# DB10005_CAN.net
KiCad netlist of a schematic drawn in Altium Designer
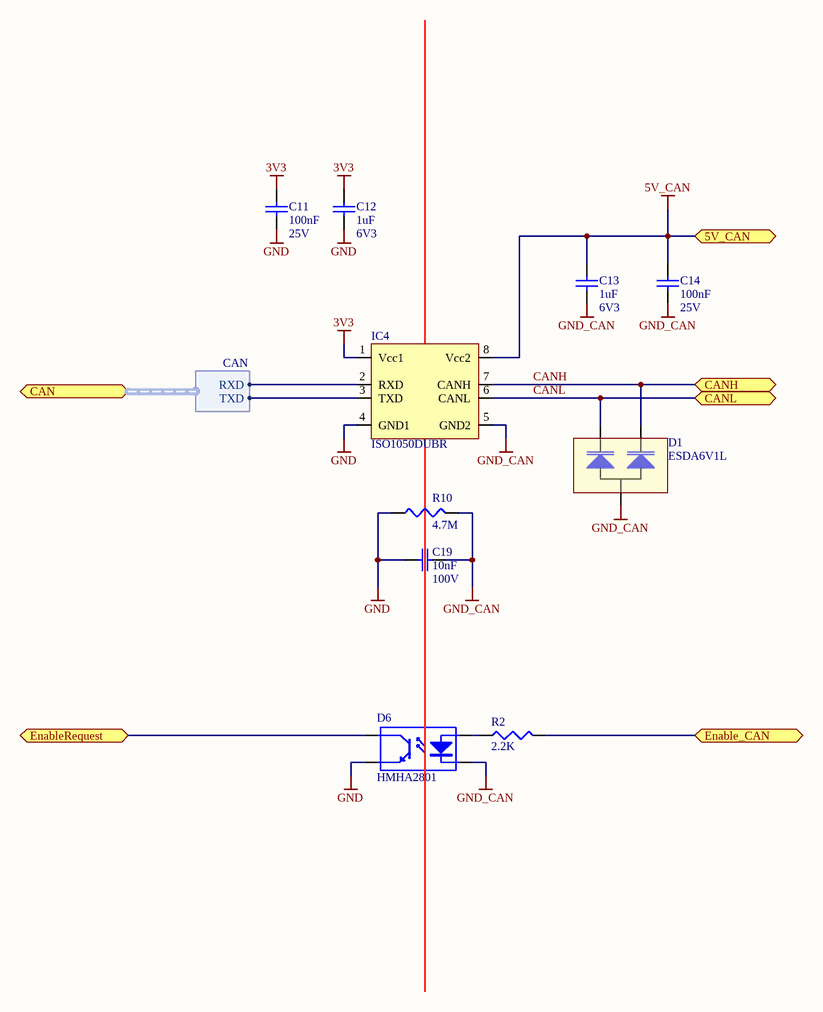
[diagram p0: DB10005_CAN.SchDoc]

(export (version "E")
  (design (tool "Eeschema 10.0.6"))
  (components
    (comp (ref "C11")
      (value "100nF")
      (footprint "C0402")
      (description "Capacitor, 100nF, 25V, X7R")
      (fields (field (name "VOLTAGE RATING") "25V"))
      (libsource (lib "AR_Capacitors_Ceramic") (part "100nF/0402/CER/25V"))
    )
    (comp (ref "C12")
      (value "1uF")
      (footprint "C0402")
      (description "Capacitor, 1uF, 6.3V, X5R")
      (fields (field (name "VOLTAGE RATING") "6V3"))
      (libsource (lib "AR_Capacitors_Ceramic") (part "1uF/0402/CER/6.3V"))
    )
    (comp (ref "C13")
      (value "1uF")
      (footprint "C0402")
      (description "Capacitor, 1uF, 6.3V, X5R")
      (fields (field (name "VOLTAGE RATING") "6V3"))
      (libsource (lib "AR_Capacitors_Ceramic") (part "1uF/0402/CER/6.3V"))
    )
    (comp (ref "C14")
      (value "100nF")
      (footprint "C0402")
      (description "Capacitor, 100nF, 25V, X7R")
      (fields (field (name "VOLTAGE RATING") "25V"))
      (libsource (lib "AR_Capacitors_Ceramic") (part "100nF/0402/CER/25V"))
    )
    (comp (ref "C19")
      (value "10nF")
      (footprint "C-0805")
      (description "Capacitor, 10nF, 100V, X7R")
      (fields (field (name "VOLTAGE RATING") "100V"))
      (libsource (lib "AR_Capacitors_Ceramic") (part "10nF/0805/CER/100V"))
    )
    (comp (ref "D1")
      (value "ESDA6V1L")
      (footprint "SOT23")
      (description "Diode TVS Dual, Vrwm: 5.25V, Vbr: 7.2V, Vc: 12.45V, Ippm: 15A")
      (libsource (lib "AR_Diodes") (part "ESDA6V1L"))
    )
    (comp (ref "D6")
      (value "HMHA2801")
      (footprint "FSOP4")
      (description "Optocoupler, Vout:80V, Iin:0.01A")
      (libsource (lib "AR_Optocouplers") (part "HMHA2801"))
    )
    (comp (ref "IC4")
      (value "ISO1050DUBR")
      (footprint "PDSO8")
      (description "CAN TRANSCEIVER")
      (libsource (lib "AR_ICs") (part "ISO1050DUBR"))
    )
    (comp (ref "R2")
      (value "2.2K")
      (footprint "0603")
      (description "Resistor, 2.2K, 1%, 0.063W, 50V, 100PPM, 0603")
      (libsource (lib "AR_Resistors_SMD") (part "2.2K/0603/0063W/50V"))
    )
    (comp (ref "R10")
      (value "4.7M")
      (footprint "0805")
      (description "Resistor, 4.7M, 1%, 0.25W, 150V, 100PPM, 0805")
      (libsource (lib "AR_Resistors_SMD") (part "4.7M/0805/0250W/150V"))
    )
  )
  (nets
    (net (code "2") (name "/CANH") (class "Default")
      (node (ref "D1") (pin "K1") (pinfunction "K1_K1") (pintype "passive"))
      (node (ref "IC4") (pin "7") (pinfunction "CANH_7") (pintype "passive"))
    )
    (net (code "3") (name "/CANL") (class "Default")
      (node (ref "D1") (pin "K2") (pinfunction "K2_K2") (pintype "passive"))
      (node (ref "IC4") (pin "6") (pinfunction "CANL_6") (pintype "passive"))
    )
    (net (code "4") (name "/EnableRequest") (class "Default")
      (node (ref "D6") (pin "4") (pinfunction "C1_4") (pintype "passive"))
    )
    (net (code "5") (name "/Enable_CAN") (class "Default")
      (node (ref "R2") (pin "2") (pinfunction "2_2") (pintype "passive"))
    )
    (net (code "6") (name "/RXD") (class "Default")
      (node (ref "IC4") (pin "2") (pinfunction "RXD_2") (pintype "passive"))
    )
    (net (code "7") (name "/TXD") (class "Default")
      (node (ref "IC4") (pin "3") (pinfunction "TXD_3") (pintype "passive"))
    )
    (net (code "9") (name "3V3") (class "Default")
      (node (ref "C11") (pin "2") (pinfunction "2_2") (pintype "passive"))
      (node (ref "C12") (pin "2") (pinfunction "2_2") (pintype "passive"))
      (node (ref "IC4") (pin "1") (pinfunction "Vcc1_1") (pintype "passive"))
    )
    (net (code "10") (name "5V_CAN") (class "Default")
      (node (ref "C13") (pin "2") (pinfunction "2_2") (pintype "passive"))
      (node (ref "C14") (pin "2") (pinfunction "2_2") (pintype "passive"))
      (node (ref "IC4") (pin "8") (pinfunction "Vcc2_8") (pintype "passive"))
    )
    (net (code "11") (name "GND") (class "Default")
      (node (ref "C11") (pin "1") (pinfunction "1_1") (pintype "passive"))
      (node (ref "C12") (pin "1") (pinfunction "1_1") (pintype "passive"))
      (node (ref "C19") (pin "1") (pinfunction "1_1") (pintype "passive"))
      (node (ref "D6") (pin "3") (pinfunction "E1_3") (pintype "passive"))
      (node (ref "IC4") (pin "4") (pinfunction "GND1_4") (pintype "passive"))
      (node (ref "R10") (pin "1") (pinfunction "1_1") (pintype "passive"))
    )
    (net (code "12") (name "GND_CAN") (class "Default")
      (node (ref "C13") (pin "1") (pinfunction "1_1") (pintype "passive"))
      (node (ref "C14") (pin "1") (pinfunction "1_1") (pintype "passive"))
      (node (ref "C19") (pin "2") (pinfunction "2_2") (pintype "passive"))
      (node (ref "D1") (pin "A") (pinfunction "A_A") (pintype "passive"))
      (node (ref "D6") (pin "2") (pinfunction "K1_2") (pintype "passive"))
      (node (ref "IC4") (pin "5") (pinfunction "GND2_5") (pintype "passive"))
      (node (ref "R10") (pin "2") (pinfunction "2_2") (pintype "passive"))
    )
    (net (code "13") (name "Net-(D6-A1)") (class "Default")
      (node (ref "D6") (pin "1") (pinfunction "A1_1") (pintype "passive"))
      (node (ref "R2") (pin "1") (pinfunction "1_1") (pintype "passive"))
    )
  )
)
